# EEZ_AUX_PS_r5B7.net
KiCad netlist of a schematic drawn in EAGLE
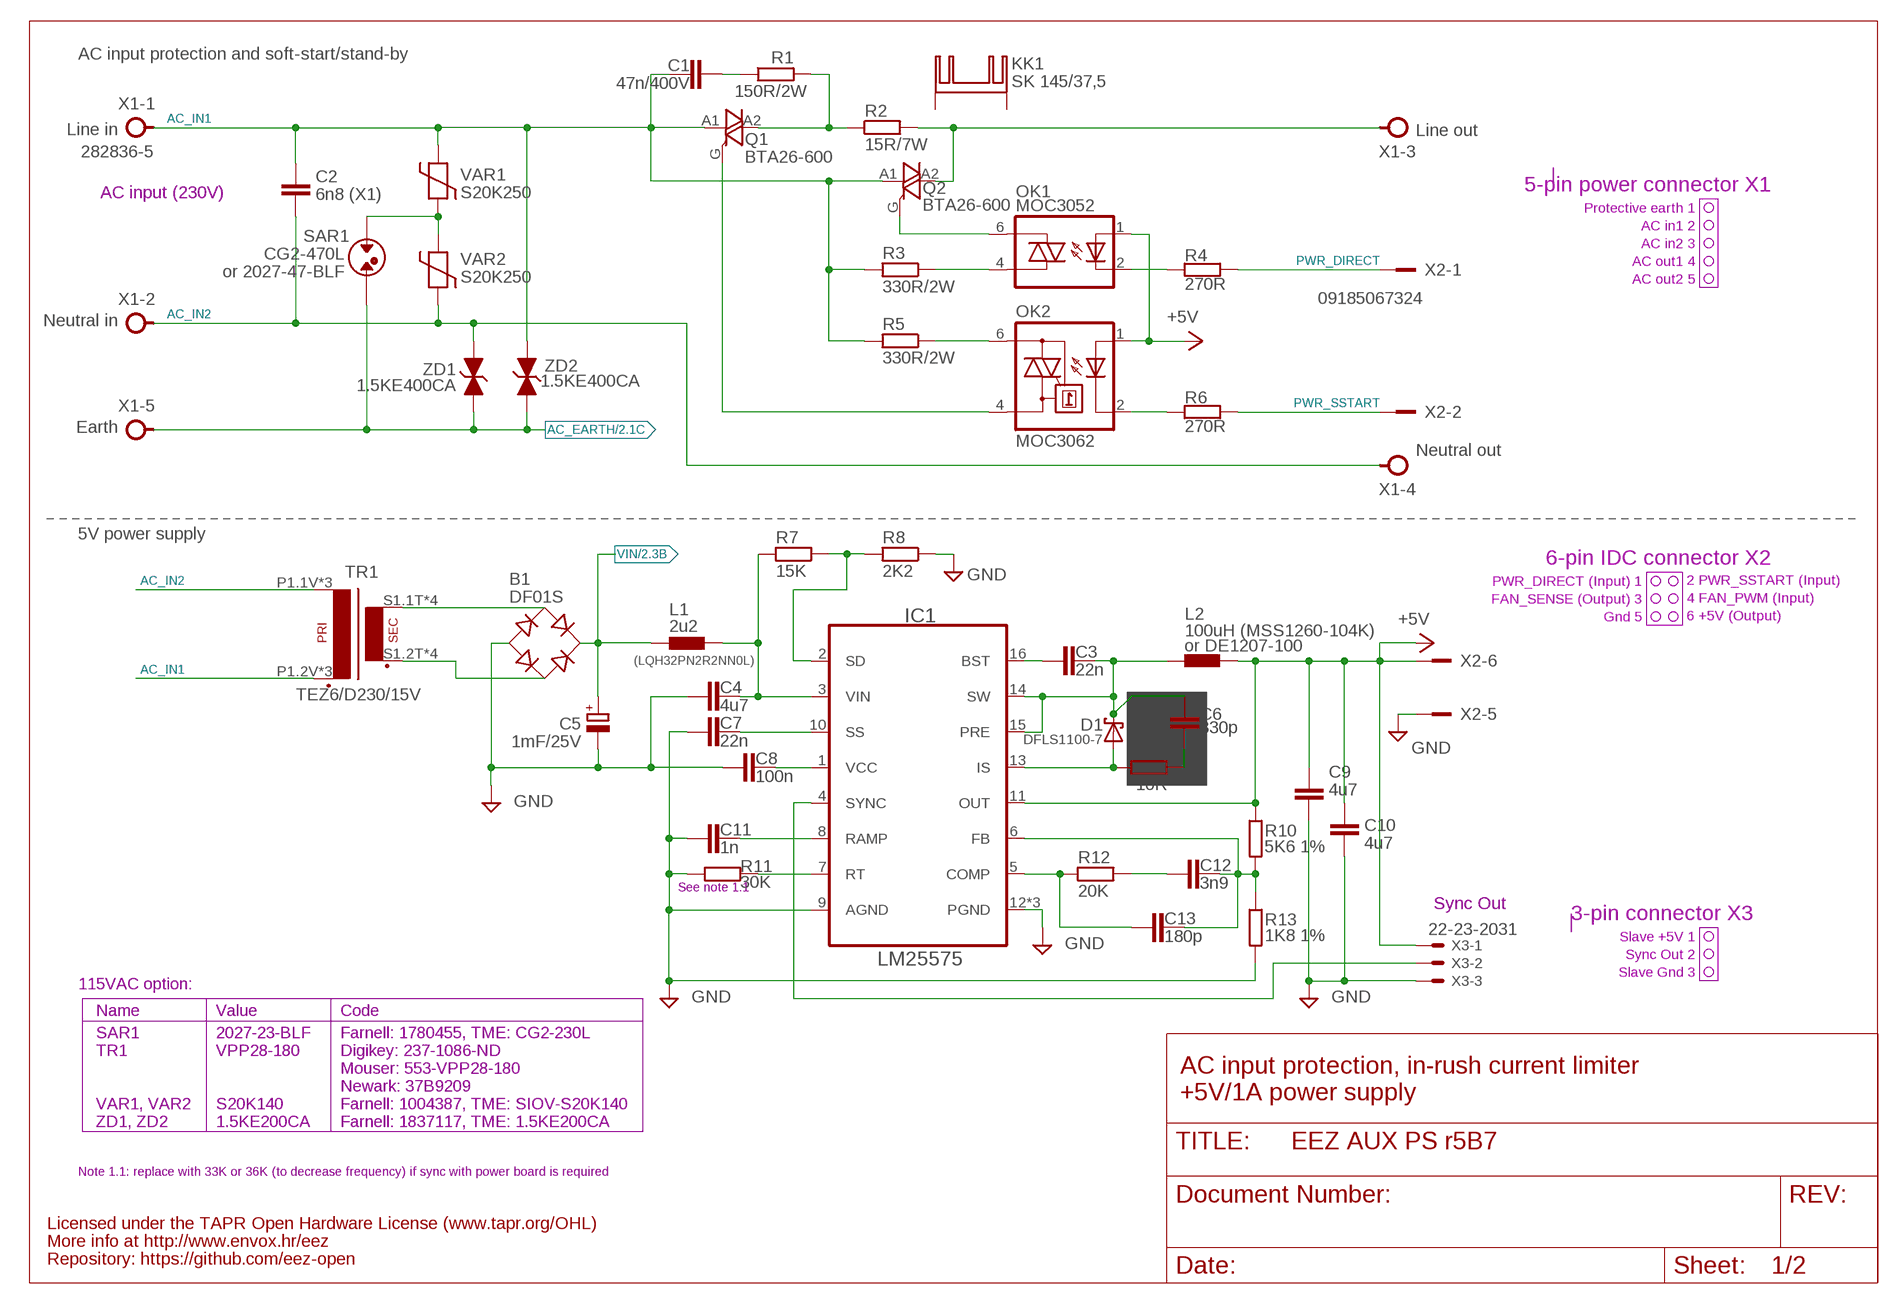
[diagram p0: schematic, sheet 1]
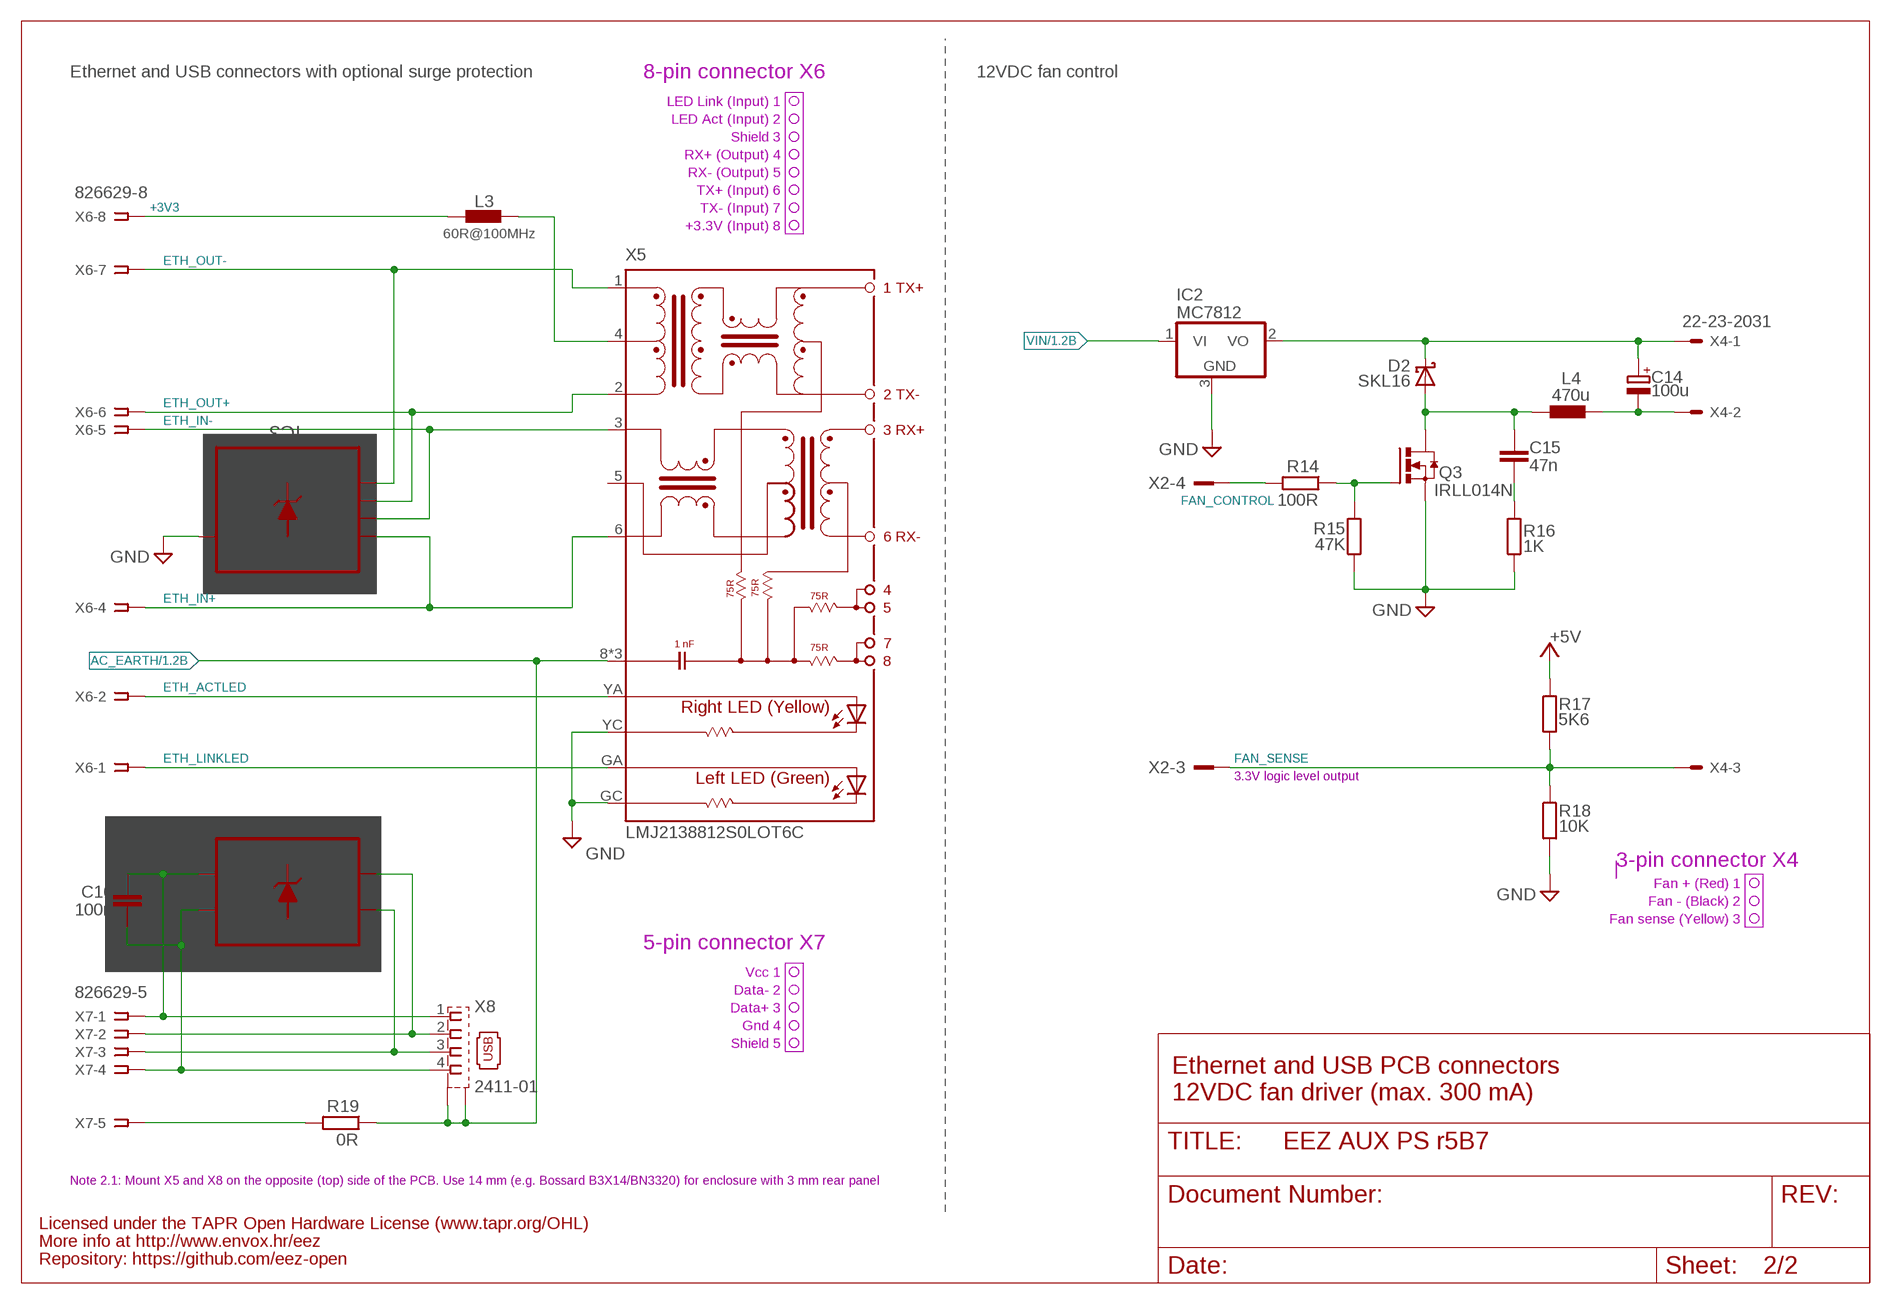
[diagram p1: schematic, sheet 2]

(export (version "E")
  (design (tool "Eeschema 10.0.6"))
  (components
    (comp (ref "B1")
      (value "DF01S")
      (footprint "eagle-import:DFS")
      (libsource (lib "eagle-import") (part "DFS01"))
    )
    (comp (ref "C1")
      (value "47n/400V")
      (footprint "eagle-import:C075-052X106")
      (libsource (lib "eagle-import") (part "C-EU075-052X106"))
    )
    (comp (ref "C2")
      (value "6n8 (X1)")
      (footprint "eagle-import:C102-064X133")
      (libsource (lib "eagle-import") (part "C-EU102-064X133"))
    )
    (comp (ref "C3")
      (value "22n")
      (footprint "eagle-import:C0805")
      (libsource (lib "eagle-import") (part "C-EUC0805"))
    )
    (comp (ref "C4")
      (value "4u7")
      (footprint "eagle-import:C1210")
      (libsource (lib "eagle-import") (part "C-EUC1210"))
    )
    (comp (ref "C5")
      (value "1mF/25V")
      (footprint "eagle-import:ECAP5_10.5")
      (libsource (lib "eagle-import") (part "ECAP5G_10.5MM"))
    )
    (comp (ref "C6")
      (value "330p")
      (footprint "eagle-import:C0805")
      (libsource (lib "eagle-import") (part "C-EUC0805"))
    )
    (comp (ref "C7")
      (value "22n")
      (footprint "eagle-import:C0805")
      (libsource (lib "eagle-import") (part "C-EUC0805"))
    )
    (comp (ref "C8")
      (value "100n")
      (footprint "eagle-import:C0805")
      (libsource (lib "eagle-import") (part "C-EUC0805"))
    )
    (comp (ref "C9")
      (value "4u7")
      (footprint "eagle-import:C1210")
      (libsource (lib "eagle-import") (part "C-EUC1210"))
    )
    (comp (ref "C10")
      (value "4u7")
      (footprint "eagle-import:C1210")
      (libsource (lib "eagle-import") (part "C-EUC1210"))
    )
    (comp (ref "C11")
      (value "1n")
      (footprint "eagle-import:C0805")
      (libsource (lib "eagle-import") (part "C-EUC0805"))
    )
    (comp (ref "C12")
      (value "3n9")
      (footprint "eagle-import:C0805")
      (libsource (lib "eagle-import") (part "C-EUC0805"))
    )
    (comp (ref "C13")
      (value "180p")
      (footprint "eagle-import:C0805")
      (libsource (lib "eagle-import") (part "C-EUC0805"))
    )
    (comp (ref "D1")
      (value "DFLS1100-7")
      (footprint "eagle-import:SOD123")
      (libsource (lib "eagle-import") (part "SCHOTTKYSOD123"))
    )
    (comp (ref "IC1")
      (value "LM25575")
      (footprint "eagle-import:SOP65P640X110-17N_HOLE")
      (libsource (lib "eagle-import") (part "LM(2)5575"))
    )
    (comp (ref "KK1")
      (value "SK 145/37,5")
      (footprint "eagle-import:SK145")
      (libsource (lib "eagle-import") (part "SK145"))
    )
    (comp (ref "L1")
      (value "2u2")
      (footprint "eagle-import:L1210")
      (libsource (lib "eagle-import") (part "L1210"))
    )
    (comp (ref "L2")
      (value "100uH (MSS1260-104K)")
      (footprint "eagle-import:MSS1278")
      (libsource (lib "eagle-import") (part "COILCRAFT_MSS1278"))
    )
    (comp (ref "OK1")
      (value "MOC3052")
      (footprint "eagle-import:DIL6-SMD")
      (libsource (lib "eagle-import") (part "MOC305X"))
    )
    (comp (ref "OK2")
      (value "MOC3062")
      (footprint "eagle-import:DIL6-SMD")
      (fields
        (field (name "MF") "FAIRCHILD SEMICONDUCTOR")
        (field (name "MPN") "MOC3033S-M")
        (field (name "MF_1") "FAIRCHILD SEMICONDUCTOR")
        (field (name "MPN_1") "MOC3033S-M")
        (field (name "OC_FARNELL") "unknown")
        (field (name "OC_NEWARK") "05C2878")
      )
      (libsource (lib "eagle-import") (part "MOC30S33"))
    )
    (comp (ref "Q1")
      (value "BTA26-600")
      (footprint "eagle-import:TOP3S-1")
      (libsource (lib "eagle-import") (part "BTA26-V"))
    )
    (comp (ref "Q2")
      (value "BTA26-600")
      (footprint "eagle-import:TOP3S-1")
      (libsource (lib "eagle-import") (part "BTA26-V"))
    )
    (comp (ref "R1")
      (value "150R/2W")
      (footprint "eagle-import:R2512")
      (libsource (lib "eagle-import") (part "R-EU_R2512"))
    )
    (comp (ref "R2")
      (value "15R/7W")
      (footprint "eagle-import:R_0913")
      (libsource (lib "eagle-import") (part "R_EU7W"))
    )
    (comp (ref "R3")
      (value "330R/2W")
      (footprint "eagle-import:R2512")
      (libsource (lib "eagle-import") (part "R-EU_R2512"))
    )
    (comp (ref "R4")
      (value "270R")
      (footprint "eagle-import:R0805")
      (libsource (lib "eagle-import") (part "R-EU_R0805"))
    )
    (comp (ref "R5")
      (value "330R/2W")
      (footprint "eagle-import:R2512")
      (libsource (lib "eagle-import") (part "R-EU_R2512"))
    )
    (comp (ref "R6")
      (value "270R")
      (footprint "eagle-import:R0805")
      (libsource (lib "eagle-import") (part "R-EU_R0805"))
    )
    (comp (ref "R7")
      (value "15K")
      (footprint "eagle-import:R0805")
      (libsource (lib "eagle-import") (part "R-EU_R0805"))
    )
    (comp (ref "R8")
      (value "2K2")
      (footprint "eagle-import:R0805")
      (libsource (lib "eagle-import") (part "R-EU_R0805"))
    )
    (comp (ref "R9")
      (value "10R")
      (footprint "eagle-import:R1206")
      (libsource (lib "eagle-import") (part "R-EU_R1206"))
    )
    (comp (ref "R10")
      (value "5K6 1%")
      (footprint "eagle-import:R0805")
      (libsource (lib "eagle-import") (part "R-EU_R0805"))
    )
    (comp (ref "R11")
      (value "30K")
      (footprint "eagle-import:R0805")
      (libsource (lib "eagle-import") (part "R-EU_R0805"))
    )
    (comp (ref "R12")
      (value "20K")
      (footprint "eagle-import:R0805")
      (libsource (lib "eagle-import") (part "R-EU_R0805"))
    )
    (comp (ref "R13")
      (value "1K8 1%")
      (footprint "eagle-import:R0805")
      (libsource (lib "eagle-import") (part "R-EU_R0805"))
    )
    (comp (ref "SAR1")
      (value "CG2-470L")
      (footprint "eagle-import:SAR")
      (libsource (lib "eagle-import") (part "SAR"))
    )
    (comp (ref "TR1")
      (value "TEZ6/D230/15V")
      (footprint "eagle-import:PCB_TRAFO6VA_TEZ+VPP")
      (libsource (lib "eagle-import") (part "PCB_TRAFO6VA_TEZ+VPP"))
    )
    (comp (ref "VAR1")
      (value "S20K250")
      (footprint "eagle-import:VARISTOR")
      (libsource (lib "eagle-import") (part "VARISTOR"))
    )
    (comp (ref "VAR2")
      (value "S20K250")
      (footprint "eagle-import:VARISTOR")
      (libsource (lib "eagle-import") (part "VARISTOR"))
    )
    (comp (ref "X1")
      (value "282836-5")
      (footprint "eagle-import:TBLOCK5.0_5")
      (libsource (lib "eagle-import") (part "TBLOCK5.0_5A"))
    )
    (comp (ref "X2")
      (value "09185067324")
      (footprint "eagle-import:IDC-6PIN")
      (libsource (lib "eagle-import") (part "IDC-6PIN"))
    )
    (comp (ref "X3")
      (value "22-23-2031")
      (footprint "eagle-import:22-23-2031")
      (fields (field (name "MF") "MOLEX"))
      (libsource (lib "eagle-import") (part "22-23-2031"))
    )
    (comp (ref "ZD1")
      (value "1.5KE400CA")
      (footprint "eagle-import:DO201-BIDIR")
      (libsource (lib "eagle-import") (part "1.5KE-BIDIR"))
    )
    (comp (ref "ZD2")
      (value "1.5KE400CA")
      (footprint "eagle-import:DO201-BIDIR")
      (libsource (lib "eagle-import") (part "1.5KE-BIDIR"))
    )
    (comp (ref "C14")
      (value "100u")
      (footprint "eagle-import:CAPAE660X610N")
      (libsource (lib "eagle-import") (part "ECAPPANASONIC_H"))
    )
    (comp (ref "C15")
      (value "47n")
      (footprint "eagle-import:C0805")
      (libsource (lib "eagle-import") (part "C-EUC0805"))
    )
    (comp (ref "C16")
      (value "100n")
      (footprint "eagle-import:C0805")
      (libsource (lib "eagle-import") (part "C-EUC0805"))
    )
    (comp (ref "D2")
      (value "SKL16")
      (footprint "eagle-import:SOD123")
      (libsource (lib "eagle-import") (part "SCHOTTKYSOD123"))
    )
    (comp (ref "IC2")
      (value "MC7812")
      (footprint "eagle-import:TO252")
      (libsource (lib "eagle-import") (part "MC78XX"))
    )
    (comp (ref "IC3")
      (value "TPD4E002DRLR")
      (footprint "eagle-import:SOT50P280X60-5N")
      (libsource (lib "eagle-import") (part "TPD4E002DRLR"))
    )
    (comp (ref "IC4")
      (value "TPD2E001DZDR")
      (footprint "eagle-import:SOP192P292X122-4N")
      (libsource (lib "eagle-import") (part "TPD2E001DZDR"))
    )
    (comp (ref "L3")
      (value "60R@100MHz")
      (footprint "eagle-import:BEAD0603")
      (libsource (lib "eagle-import") (part "FERRITE_BEAD0603"))
    )
    (comp (ref "L4")
      (value "470u")
      (footprint "eagle-import:DE0704")
      (libsource (lib "eagle-import") (part "DE0704"))
    )
    (comp (ref "Q3")
      (value "IRLL014N")
      (footprint "eagle-import:SOT223")
      (libsource (lib "eagle-import") (part "N-HEXFET-2D_?-SOT232IRLL014N"))
    )
    (comp (ref "R14")
      (value "100R")
      (footprint "eagle-import:R0805")
      (libsource (lib "eagle-import") (part "R-EU_R0805"))
    )
    (comp (ref "R15")
      (value "47K")
      (footprint "eagle-import:R0805")
      (libsource (lib "eagle-import") (part "R-EU_R0805"))
    )
    (comp (ref "R16")
      (value "1K")
      (footprint "eagle-import:R0805")
      (libsource (lib "eagle-import") (part "R-EU_R0805"))
    )
    (comp (ref "R17")
      (value "5K6")
      (footprint "eagle-import:R0805")
      (libsource (lib "eagle-import") (part "R-EU_R0805"))
    )
    (comp (ref "R18")
      (value "10K")
      (footprint "eagle-import:R0805")
      (libsource (lib "eagle-import") (part "R-EU_R0805"))
    )
    (comp (ref "R19")
      (value "0R")
      (footprint "eagle-import:R0805")
      (libsource (lib "eagle-import") (part "R-EU_R0805"))
    )
    (comp (ref "X4")
      (value "22-23-2031")
      (footprint "eagle-import:22-23-2031")
      (fields (field (name "MF") "MOLEX"))
      (libsource (lib "eagle-import") (part "22-23-2031"))
    )
    (comp (ref "X5")
      (value "LMJ2138812S0LOT6C")
      (footprint "eagle-import:RJ45-VERT")
      (libsource (lib "eagle-import") (part "RJ45-VERT"))
    )
    (comp (ref "X6")
      (value "826629-8")
      (footprint "eagle-import:SSW-108-02-S-S")
      (fields (field (name "MPN") "SSW-108-02-S-S"))
      (libsource (lib "eagle-import") (part "SSW-108-02-S-S"))
    )
    (comp (ref "X7")
      (value "826629-5")
      (footprint "eagle-import:SSW-105-02-S-S")
      (fields (field (name "MPN") "SSW-105-02-S-S"))
      (libsource (lib "eagle-import") (part "SSW-105-02-S-S"))
    )
    (comp (ref "X8")
      (value "2411-01")
      (footprint "eagle-import:KUSBVX-BS1N")
      (libsource (lib "eagle-import") (part "KUSBVX-BS1N"))
    )
  )
  (nets
    (net (code "1") (name "+3V3") (class "Default")
      (node (ref "L3") (pin "P$2") (pinfunction "2_P$2") (pintype "passive"))
      (node (ref "X6") (pin "8") (pinfunction "1_8") (pintype "passive"))
    )
    (net (code "2") (name "+5V") (class "Default")
      (node (ref "C10") (pin "1") (pinfunction "1_1") (pintype "passive"))
      (node (ref "C9") (pin "1") (pinfunction "1_1") (pintype "passive"))
      (node (ref "IC1") (pin "11") (pinfunction "OUT_11") (pintype "output"))
      (node (ref "L2") (pin "2") (pinfunction "2_2") (pintype "passive"))
      (node (ref "OK1") (pin "1") (pinfunction "A_1") (pintype "passive"))
      (node (ref "OK2") (pin "1") (pinfunction "A_1") (pintype "passive"))
      (node (ref "R10") (pin "1") (pinfunction "1_1") (pintype "passive"))
      (node (ref "R17") (pin "1") (pinfunction "1_1") (pintype "passive"))
      (node (ref "X2") (pin "6") (pinfunction "1_6") (pintype "passive"))
      (node (ref "X3") (pin "1") (pinfunction "S_1") (pintype "passive"))
    )
    (net (code "3") (name "AC_EARTH") (class "Default")
      (node (ref "R19") (pin "1") (pinfunction "1_1") (pintype "passive"))
      (node (ref "SAR1") (pin "P$2") (pinfunction "P$2_P$2") (pintype "bidirectional"))
      (node (ref "X1") (pin "5") (pinfunction "1_5") (pintype "bidirectional"))
      (node (ref "X5") (pin "8") (pinfunction "SH_8") (pintype "input"))
      (node (ref "X5") (pin "SH1") (pinfunction "SH_SH1") (pintype "input"))
      (node (ref "X5") (pin "SH2") (pinfunction "SH_SH2") (pintype "input"))
      (node (ref "X8") (pin "M1") (pinfunction "S1_M1") (pintype "passive"))
      (node (ref "X8") (pin "M2") (pinfunction "S2_M2") (pintype "passive"))
      (node (ref "ZD1") (pin "C") (pinfunction "1_C") (pintype "passive"))
      (node (ref "ZD2") (pin "C") (pinfunction "1_C") (pintype "passive"))
    )
    (net (code "4") (name "AC_IN1") (class "Default")
      (node (ref "C1") (pin "2") (pinfunction "2_2") (pintype "passive"))
      (node (ref "C2") (pin "1") (pinfunction "1_1") (pintype "passive"))
      (node (ref "Q1") (pin "A1") (pinfunction "A1_A1") (pintype "passive"))
      (node (ref "Q2") (pin "A1") (pinfunction "A1_A1") (pintype "passive"))
      (node (ref "R3") (pin "2") (pinfunction "2_2") (pintype "passive"))
      (node (ref "R5") (pin "2") (pinfunction "2_2") (pintype "passive"))
      (node (ref "TR1") (pin "P1.2V") (pinfunction "P2_P1.2V") (pintype "passive"))
      (node (ref "TR1") (pin "P2.2V") (pinfunction "P2_P2.2V") (pintype "passive"))
      (node (ref "TR1") (pin "P2_TEZ") (pinfunction "P2_P2_TEZ") (pintype "passive"))
      (node (ref "VAR1") (pin "P$2") (pinfunction "P$2_P$2") (pintype "bidirectional"))
      (node (ref "X1") (pin "1") (pinfunction "1_1") (pintype "bidirectional"))
      (node (ref "ZD2") (pin "A") (pinfunction "2_A") (pintype "passive"))
    )
    (net (code "5") (name "AC_IN2") (class "Default")
      (node (ref "C2") (pin "2") (pinfunction "2_2") (pintype "passive"))
      (node (ref "TR1") (pin "P1.1V") (pinfunction "P1_P1.1V") (pintype "passive"))
      (node (ref "TR1") (pin "P1_TEZ") (pinfunction "P1_P1_TEZ") (pintype "passive"))
      (node (ref "TR1") (pin "P2.1V") (pinfunction "P1_P2.1V") (pintype "passive"))
      (node (ref "VAR2") (pin "P$1") (pinfunction "P$1_P$1") (pintype "bidirectional"))
      (node (ref "X1") (pin "2") (pinfunction "1_2") (pintype "bidirectional"))
      (node (ref "X1") (pin "4") (pinfunction "1_4") (pintype "bidirectional"))
      (node (ref "ZD1") (pin "A") (pinfunction "2_A") (pintype "passive"))
    )
    (net (code "6") (name "ETH_ACTLED") (class "Default")
      (node (ref "X5") (pin "YA") (pinfunction "YELLOW_A_YA") (pintype "passive"))
      (node (ref "X6") (pin "2") (pinfunction "1_2") (pintype "passive"))
    )
    (net (code "7") (name "ETH_IN+") (class "Default")
      (node (ref "IC3") (pin "5") (pinfunction "IO4_5") (pintype "bidirectional"))
      (node (ref "X5") (pin "6") (pinfunction "RD-_6") (pintype "input"))
      (node (ref "X6") (pin "4") (pinfunction "1_4") (pintype "passive"))
    )
    (net (code "8") (name "ETH_IN-") (class "Default")
      (node (ref "IC3") (pin "4") (pinfunction "IO3_4") (pintype "bidirectional"))
      (node (ref "X5") (pin "3") (pinfunction "RD+_3") (pintype "input"))
      (node (ref "X6") (pin "5") (pinfunction "1_5") (pintype "passive"))
    )
    (net (code "9") (name "ETH_LINKLED") (class "Default")
      (node (ref "X5") (pin "GA") (pinfunction "GREEN-A_GA") (pintype "passive"))
      (node (ref "X6") (pin "1") (pinfunction "1_1") (pintype "passive"))
    )
    (net (code "10") (name "ETH_OUT+") (class "Default")
      (node (ref "IC3") (pin "3") (pinfunction "IO2_3") (pintype "bidirectional"))
      (node (ref "X5") (pin "2") (pinfunction "TD-_2") (pintype "input"))
      (node (ref "X6") (pin "6") (pinfunction "1_6") (pintype "passive"))
    )
    (net (code "11") (name "ETH_OUT-") (class "Default")
      (node (ref "IC3") (pin "1") (pinfunction "IO1_1") (pintype "bidirectional"))
      (node (ref "X5") (pin "1") (pinfunction "TD+_1") (pintype "input"))
      (node (ref "X6") (pin "7") (pinfunction "1_7") (pintype "passive"))
    )
    (net (code "12") (name "FAN_CONTROL") (class "Default")
      (node (ref "R14") (pin "2") (pinfunction "2_2") (pintype "passive"))
      (node (ref "X2") (pin "4") (pinfunction "1_4") (pintype "passive"))
    )
    (net (code "13") (name "FAN_SENSE") (class "Default")
      (node (ref "R17") (pin "2") (pinfunction "2_2") (pintype "passive"))
      (node (ref "R18") (pin "1") (pinfunction "1_1") (pintype "passive"))
      (node (ref "X2") (pin "3") (pinfunction "1_3") (pintype "passive"))
      (node (ref "X4") (pin "3") (pinfunction "S_3") (pintype "passive"))
    )
    (net (code "14") (name "GND") (class "Default")
      (node (ref "B1") (pin "-") (pinfunction "-_-") (pintype "passive"))
      (node (ref "C10") (pin "2") (pinfunction "2_2") (pintype "passive"))
      (node (ref "C11") (pin "1") (pinfunction "1_1") (pintype "passive"))
      (node (ref "C4") (pin "2") (pinfunction "2_2") (pintype "passive"))
      (node (ref "C5") (pin "-") (pinfunction "-_-") (pintype "passive"))
      (node (ref "C7") (pin "2") (pinfunction "2_2") (pintype "passive"))
      (node (ref "C8") (pin "1") (pinfunction "1_1") (pintype "passive"))
      (node (ref "C9") (pin "2") (pinfunction "2_2") (pintype "passive"))
      (node (ref "IC1") (pin "12") (pinfunction "PGND_12") (pintype "passive"))
      (node (ref "IC1") (pin "9") (pinfunction "AGND_9") (pintype "passive"))
      (node (ref "IC1") (pin "TP") (pinfunction "PGND_TP") (pintype "passive"))
      (node (ref "IC1") (pin "TP2") (pinfunction "PGND_TP2") (pintype "passive"))
      (node (ref "IC2") (pin "3") (pinfunction "GND_3") (pintype "passive"))
      (node (ref "IC3") (pin "2") (pinfunction "GND_2") (pintype "passive"))
      (node (ref "Q3") (pin "3") (pinfunction "S_3") (pintype "passive"))
      (node (ref "R11") (pin "2") (pinfunction "2_2") (pintype "passive"))
      (node (ref "R13") (pin "2") (pinfunction "2_2") (pintype "passive"))
      (node (ref "R15") (pin "1") (pinfunction "1_1") (pintype "passive"))
      (node (ref "R16") (pin "1") (pinfunction "1_1") (pintype "passive"))
      (node (ref "R18") (pin "2") (pinfunction "2_2") (pintype "passive"))
      (node (ref "R8") (pin "1") (pinfunction "1_1") (pintype "passive"))
      (node (ref "X2") (pin "5") (pinfunction "1_5") (pintype "passive"))
      (node (ref "X3") (pin "3") (pinfunction "S_3") (pintype "passive"))
      (node (ref "X5") (pin "GC") (pinfunction "GREEN-C_GC") (pintype "passive"))
      (node (ref "X5") (pin "YC") (pinfunction "YELLOW-C_YC") (pintype "passive"))
    )
    (net (code "15") (name "Net-(B1-PadAC1)") (class "Default")
      (node (ref "B1") (pin "AC1") (pinfunction "AC1_AC1") (pintype "passive"))
      (node (ref "TR1") (pin "S1.1T") (pinfunction "S1_S1.1T") (pintype "passive"))
      (node (ref "TR1") (pin "S1.1V") (pinfunction "S1_S1.1V") (pintype "passive"))
      (node (ref "TR1") (pin "S2.1T") (pinfunction "S1_S2.1T") (pintype "passive"))
      (node (ref "TR1") (pin "S2.1V") (pinfunction "S1_S2.1V") (pintype "passive"))
    )
    (net (code "16") (name "Net-(B1-PadAC2)") (class "Default")
      (node (ref "B1") (pin "AC2") (pinfunction "AC2_AC2") (pintype "passive"))
      (node (ref "TR1") (pin "S1.2T") (pinfunction "S2_S1.2T") (pintype "passive"))
      (node (ref "TR1") (pin "S1.2V") (pinfunction "S2_S1.2V") (pintype "passive"))
      (node (ref "TR1") (pin "S2.2T") (pinfunction "S2_S2.2T") (pintype "passive"))
      (node (ref "TR1") (pin "S2.2V") (pinfunction "S2_S2.2V") (pintype "passive"))
    )
    (net (code "17") (name "Net-(C1-Pad1)") (class "Default")
      (node (ref "C1") (pin "1") (pinfunction "1_1") (pintype "passive"))
      (node (ref "R1") (pin "1") (pinfunction "1_1") (pintype "passive"))
    )
    (net (code "18") (name "Net-(C6-Pad2)") (class "Default")
      (node (ref "C6") (pin "2") (pinfunction "2_2") (pintype "passive"))
      (node (ref "R9") (pin "2") (pinfunction "2_2") (pintype "passive"))
    )
    (net (code "19") (name "Net-(C12-Pad2)") (class "Default")
      (node (ref "C12") (pin "2") (pinfunction "2_2") (pintype "passive"))
      (node (ref "R12") (pin "2") (pinfunction "2_2") (pintype "passive"))
    )
    (net (code "20") (name "Net-(C14-+)") (class "Default")
      (node (ref "C14") (pin "1") (pinfunction "+_1") (pintype "passive"))
      (node (ref "D2") (pin "C") (pinfunction "C_C") (pintype "passive"))
      (node (ref "IC2") (pin "2") (pinfunction "VO_2") (pintype "passive"))
      (node (ref "X4") (pin "1") (pinfunction "S_1") (pintype "passive"))
    )
    (net (code "21") (name "Net-(C14--)") (class "Default")
      (node (ref "C14") (pin "2") (pinfunction "-_2") (pintype "passive"))
      (node (ref "L4") (pin "1") (pinfunction "1_1") (pintype "passive"))
      (node (ref "X4") (pin "2") (pinfunction "S_2") (pintype "passive"))
    )
    (net (code "22") (name "Net-(C15-Pad1)") (class "Default")
      (node (ref "C15") (pin "1") (pinfunction "1_1") (pintype "passive"))
      (node (ref "R16") (pin "2") (pinfunction "2_2") (pintype "passive"))
    )
    (net (code "23") (name "Net-(C15-Pad2)") (class "Default")
      (node (ref "C15") (pin "2") (pinfunction "2_2") (pintype "passive"))
      (node (ref "D2") (pin "A") (pinfunction "A_A") (pintype "passive"))
      (node (ref "L4") (pin "2") (pinfunction "2_2") (pintype "passive"))
      (node (ref "Q3") (pin "2") (pinfunction "D_2") (pintype "passive"))
      (node (ref "Q3") (pin "4") (pinfunction "D_4") (pintype "passive"))
    )
    (net (code "24") (name "Net-(IC1-BST)") (class "Default")
      (node (ref "C3") (pin "2") (pinfunction "2_2") (pintype "passive"))
      (node (ref "IC1") (pin "16") (pinfunction "BST_16") (pintype "input"))
    )
    (net (code "25") (name "Net-(IC1-COMP)") (class "Default")
      (node (ref "C13") (pin "2") (pinfunction "2_2") (pintype "passive"))
      (node (ref "IC1") (pin "5") (pinfunction "COMP_5") (pintype "input"))
      (node (ref "R12") (pin "1") (pinfunction "1_1") (pintype "passive"))
    )
    (net (code "26") (name "Net-(IC1-FB)") (class "Default")
      (node (ref "C12") (pin "1") (pinfunction "1_1") (pintype "passive"))
      (node (ref "C13") (pin "1") (pinfunction "1_1") (pintype "passive"))
      (node (ref "IC1") (pin "6") (pinfunction "FB_6") (pintype "input"))
      (node (ref "R10") (pin "2") (pinfunction "2_2") (pintype "passive"))
      (node (ref "R13") (pin "1") (pinfunction "1_1") (pintype "passive"))
    )
    (net (code "27") (name "Net-(IC1-IS)") (class "Default")
      (node (ref "D1") (pin "A") (pinfunction "A_A") (pintype "passive"))
      (node (ref "IC1") (pin "13") (pinfunction "IS_13") (pintype "input"))
      (node (ref "R9") (pin "1") (pinfunction "1_1") (pintype "passive"))
    )
    (net (code "28") (name "Net-(IC1-PRE)") (class "Default")
      (node (ref "C3") (pin "1") (pinfunction "1_1") (pintype "passive"))
      (node (ref "C6") (pin "1") (pinfunction "1_1") (pintype "passive"))
      (node (ref "D1") (pin "C") (pinfunction "C_C") (pintype "passive"))
      (node (ref "IC1") (pin "14") (pinfunction "SW_14") (pintype "output"))
      (node (ref "IC1") (pin "15") (pinfunction "PRE_15") (pintype "input"))
      (node (ref "L2") (pin "1") (pinfunction "1_1") (pintype "passive"))
    )
    (net (code "29") (name "Net-(IC1-RAMP)") (class "Default")
      (node (ref "C11") (pin "2") (pinfunction "2_2") (pintype "passive"))
      (node (ref "IC1") (pin "8") (pinfunction "RAMP_8") (pintype "input"))
    )
    (net (code "30") (name "Net-(IC1-RT)") (class "Default")
      (node (ref "IC1") (pin "7") (pinfunction "RT_7") (pintype "input"))
      (node (ref "R11") (pin "1") (pinfunction "1_1") (pintype "passive"))
    )
    (net (code "31") (name "Net-(IC1-SD)") (class "Default")
      (node (ref "IC1") (pin "2") (pinfunction "SD_2") (pintype "input"))
      (node (ref "R7") (pin "1") (pinfunction "1_1") (pintype "passive"))
      (node (ref "R8") (pin "2") (pinfunction "2_2") (pintype "passive"))
    )
    (net (code "32") (name "Net-(IC1-SS)") (class "Default")
      (node (ref "C7") (pin "1") (pinfunction "1_1") (pintype "passive"))
      (node (ref "IC1") (pin "10") (pinfunction "SS_10") (pintype "input"))
    )
    (net (code "33") (name "Net-(IC1-SYNC)") (class "Default")
      (node (ref "IC1") (pin "4") (pinfunction "SYNC_4") (pintype "input"))
      (node (ref "X3") (pin "2") (pinfunction "S_2") (pintype "passive"))
    )
    (net (code "34") (name "Net-(IC1-VCC)") (class "Default")
      (node (ref "C8") (pin "2") (pinfunction "2_2") (pintype "passive"))
      (node (ref "IC1") (pin "1") (pinfunction "VCC_1") (pintype "power_in"))
    )
    (net (code "35") (name "Net-(IC1-VIN)") (class "Default")
      (node (ref "C4") (pin "1") (pinfunction "1_1") (pintype "passive"))
      (node (ref "IC1") (pin "3") (pinfunction "VIN_3") (pintype "input"))
      (node (ref "L1") (pin "2") (pinfunction "2_2") (pintype "passive"))
      (node (ref "R7") (pin "2") (pinfunction "2_2") (pintype "passive"))
    )
    (net (code "36") (name "Net-(IC4-GND)") (class "Default")
      (node (ref "C16") (pin "1") (pinfunction "1_1") (pintype "passive"))
      (node (ref "IC4") (pin "1") (pinfunction "GND_1") (pintype "passive"))
      (node (ref "X7") (pin "4") (pinfunction "1_4") (pintype "passive"))
      (node (ref "X8") (pin "4") (pinfunction "4_4") (pintype "passive"))
    )
    (net (code "37") (name "Net-(IC4-IO1)") (class "Default")
      (node (ref "IC4") (pin "2") (pinfunction "IO1_2") (pintype "bidirectional"))
      (node (ref "X7") (pin "2") (pinfunction "1_2") (pintype "passive"))
      (node (ref "X8") (pin "2") (pinfunction "2_2") (pintype "passive"))
    )
    (net (code "38") (name "Net-(IC4-IO2)") (class "Default")
      (node (ref "IC4") (pin "3") (pinfunction "IO2_3") (pintype "bidirectional"))
      (node (ref "X7") (pin "3") (pinfunction "1_3") (pintype "passive"))
      (node (ref "X8") (pin "3") (pinfunction "3_3") (pintype "passive"))
    )
    (net (code "39") (name "Net-(IC4-VCC)") (class "Default")
      (node (ref "C16") (pin "2") (pinfunction "2_2") (pintype "passive"))
      (node (ref "IC4") (pin "4") (pinfunction "VCC_4") (pintype "power_in"))
      (node (ref "X7") (pin "1") (pinfunction "1_1") (pintype "passive"))
      (node (ref "X8") (pin "1") (pinfunction "1_1") (pintype "passive"))
    )
    (net (code "40") (name "Net-(L3-1)") (class "Default")
      (node (ref "L3") (pin "P$1") (pinfunction "1_P$1") (pintype "passive"))
      (node (ref "X5") (pin "4") (pinfunction "CT_4") (pintype "input"))
    )
    (net (code "41") (name "Net-(OK1-A1)") (class "Default")
      (node (ref "OK1") (pin "4") (pinfunction "A1_4") (pintype "passive"))
      (node (ref "R3") (pin "1") (pinfunction "1_1") (pintype "passive"))
    )
    (net (code "42") (name "Net-(OK1-A2)") (class "Default")
      (node (ref "OK1") (pin "6") (pinfunction "A2_6") (pintype "passive"))
      (node (ref "Q2") (pin "G") (pinfunction "G_G") (pintype "passive"))
    )
    (net (code "43") (name "Net-(OK1-C)") (class "Default")
      (node (ref "OK1") (pin "2") (pinfunction "C_2") (pintype "passive"))
      (node (ref "R4") (pin "1") (pinfunction "1_1") (pintype "passive"))
    )
    (net (code "44") (name "Net-(OK2-A1)") (class "Default")
      (node (ref "OK2") (pin "4") (pinfunction "A1_4") (pintype "passive"))
      (node (ref "Q1") (pin "G") (pinfunction "G_G") (pintype "passive"))
    )
    (net (code "45") (name "Net-(OK2-A2)") (class "Default")
      (node (ref "OK2") (pin "6") (pinfunction "A2_6") (pintype "passive"))
      (node (ref "R5") (pin "1") (pinfunction "1_1") (pintype "passive"))
    )
    (net (code "46") (name "Net-(OK2-C)") (class "Default")
      (node (ref "OK2") (pin "2") (pinfunction "C_2") (pintype "passive"))
      (node (ref "R6") (pin "1") (pinfunction "1_1") (pintype "passive"))
    )
    (net (code "47") (name "Net-(Q1-PadA2)") (class "Default")
      (node (ref "Q1") (pin "A2") (pinfunction "A2_A2") (pintype "passive"))
      (node (ref "R1") (pin "2") (pinfunction "2_2") (pintype "passive"))
      (node (ref "R2") (pin "1") (pinfunction "1_1") (pintype "passive"))
    )
    (net (code "48") (name "Net-(Q3-G)") (class "Default")
      (node (ref "Q3") (pin "1") (pinfunction "G_1") (pintype "passive"))
      (node (ref "R14") (pin "1") (pinfunction "1_1") (pintype "passive"))
      (node (ref "R15") (pin "2") (pinfunction "2_2") (pintype "passive"))
    )
    (net (code "49") (name "Net-(SAR1-PadP$1)") (class "Default")
      (node (ref "SAR1") (pin "P$1") (pinfunction "P$1_P$1") (pintype "bidirectional"))
      (node (ref "VAR1") (pin "P$1") (pinfunction "P$1_P$1") (pintype "bidirectional"))
      (node (ref "VAR2") (pin "P$2") (pinfunction "P$2_P$2") (pintype "bidirectional"))
    )
    (net (code "50") (name "Net-(X1C-1)") (class "Default")
      (node (ref "Q2") (pin "A2") (pinfunction "A2_A2") (pintype "passive"))
      (node (ref "R2") (pin "2") (pinfunction "2_2") (pintype "passive"))
      (node (ref "X1") (pin "3") (pinfunction "1_3") (pintype "bidirectional"))
    )
    (net (code "51") (name "Net-(X7E-1)") (class "Default")
      (node (ref "R19") (pin "2") (pinfunction "2_2") (pintype "passive"))
      (node (ref "X7") (pin "5") (pinfunction "1_5") (pintype "passive"))
    )
    (net (code "52") (name "PWR_DIRECT") (class "Default")
      (node (ref "R4") (pin "2") (pinfunction "2_2") (pintype "passive"))
      (node (ref "X2") (pin "1") (pinfunction "1_1") (pintype "passive"))
    )
    (net (code "53") (name "PWR_SSTART") (class "Default")
      (node (ref "R6") (pin "2") (pinfunction "2_2") (pintype "passive"))
      (node (ref "X2") (pin "2") (pinfunction "1_2") (pintype "passive"))
    )
    (net (code "54") (name "VIN") (class "Default")
      (node (ref "B1") (pin "+") (pinfunction "+_+") (pintype "passive"))
      (node (ref "C5") (pin "+") (pinfunction "+_+") (pintype "passive"))
      (node (ref "IC2") (pin "1") (pinfunction "VI_1") (pintype "input"))
      (node (ref "L1") (pin "1") (pinfunction "1_1") (pintype "passive"))
    )
    (net (code "55") (name "unconnected-(KK1-K-Pad1)") (class "Default")
      (node (ref "KK1") (pin "1") (pinfunction "K_1") (pintype "passive"))
    )
    (net (code "56") (name "unconnected-(KK1-K-Pad2)") (class "Default")
      (node (ref "KK1") (pin "2") (pinfunction "K_2") (pintype "passive"))
    )
    (net (code "57") (name "unconnected-(X5-CR-Pad5)") (class "Default")
      (node (ref "X5") (pin "5") (pinfunction "CR_5") (pintype "input"))
    )
  )
)
